# ServoControllerCircuit.net
KiCad netlist of a schematic drawn in EAGLE
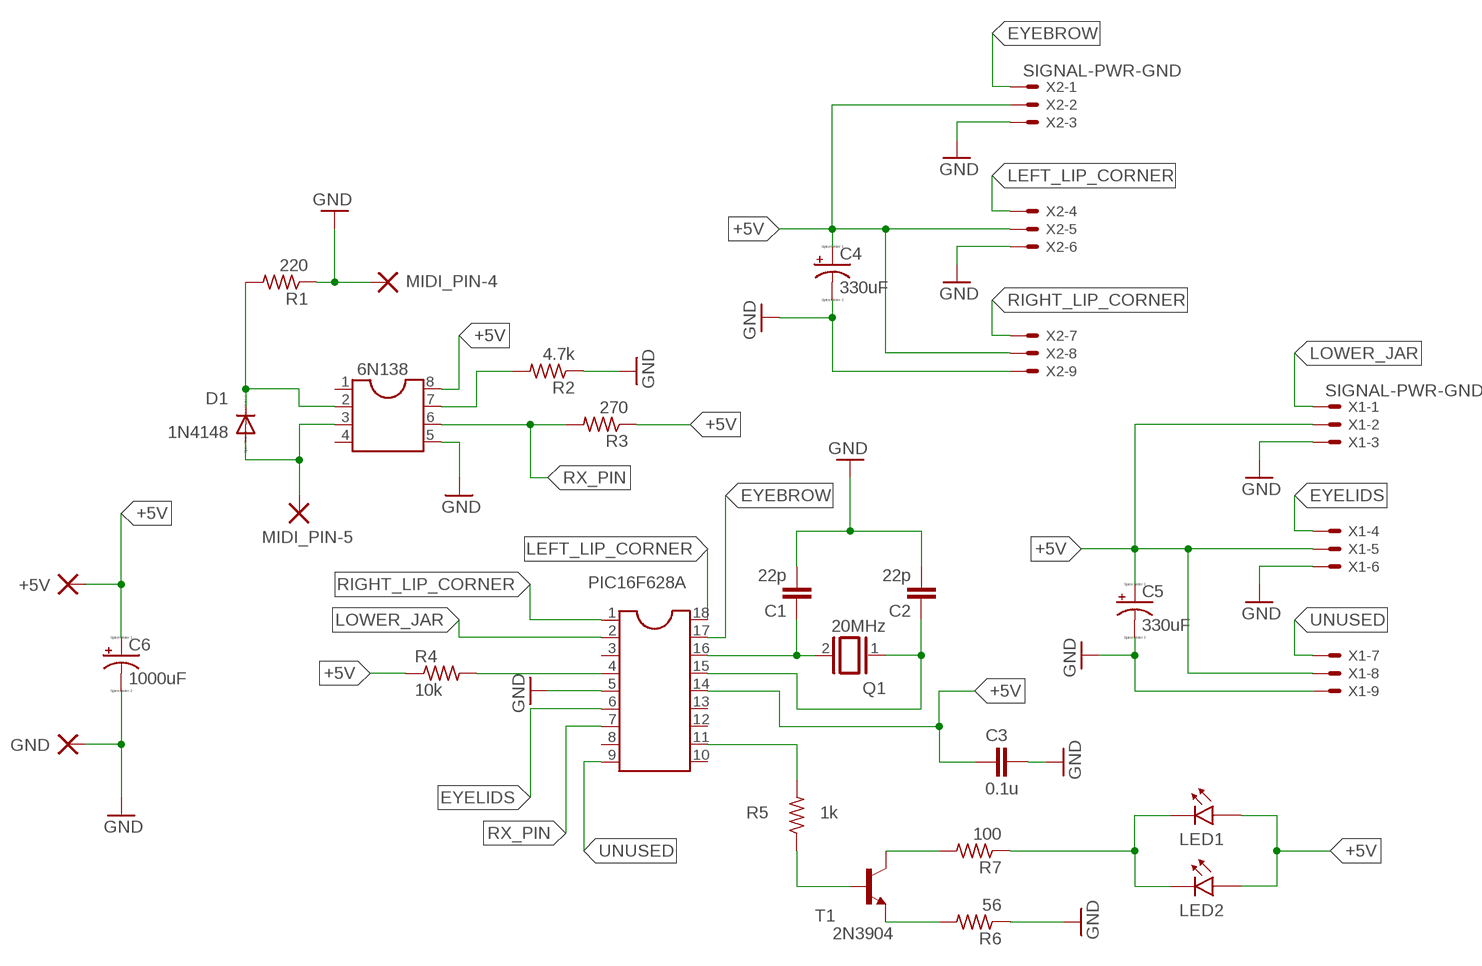
[diagram p0: schematic, sheet 1]

(export (version "E")
  (design (tool "Eeschema 10.0.6"))
  (components
    (comp (ref "+5V")
      (value "DOUBLE_THROUGH_HOLE_PAD")
      (footprint "eagle-import:DOUBLE_THROUGH_HOLE_PAD")
      (libsource (lib "eagle-import") (part "DOUBLE_THROUGH_HOLE_PAD"))
    )
    (comp (ref "6N138")
      (value "DIL8S")
      (footprint "eagle-import:SOCKET-08")
      (libsource (lib "eagle-import") (part "DIL8S"))
    )
    (comp (ref "C1")
      (value "22p")
      (footprint "eagle-import:C050-025X075")
      (libsource (lib "eagle-import") (part "C-EU050-025X075"))
    )
    (comp (ref "C2")
      (value "22p")
      (footprint "eagle-import:C050-025X075")
      (libsource (lib "eagle-import") (part "C-EU050-025X075"))
    )
    (comp (ref "C3")
      (value "0.1u")
      (footprint "eagle-import:C050-025X075")
      (libsource (lib "eagle-import") (part "C-EU050-025X075"))
    )
    (comp (ref "C4")
      (value "330uF")
      (footprint "eagle-import:E3,5-8")
      (libsource (lib "eagle-import") (part "CPOL-USE3.5-8"))
    )
    (comp (ref "C5")
      (value "330uF")
      (footprint "eagle-import:E3,5-8")
      (libsource (lib "eagle-import") (part "CPOL-USE3.5-8"))
    )
    (comp (ref "C6")
      (value "1000uF")
      (footprint "eagle-import:E5-10,5")
      (libsource (lib "eagle-import") (part "CPOL-USE5-10.5"))
    )
    (comp (ref "D1")
      (value "1N4148")
      (footprint "eagle-import:DO35-10")
      (libsource (lib "eagle-import") (part "1N4148DO35-10"))
    )
    (comp (ref "GND")
      (value "DOUBLE_THROUGH_HOLE_PAD")
      (footprint "eagle-import:DOUBLE_THROUGH_HOLE_PAD")
      (libsource (lib "eagle-import") (part "DOUBLE_THROUGH_HOLE_PAD"))
    )
    (comp (ref "LED1")
      (value "REMOTE_LED")
      (footprint "eagle-import:REMOTE_LED")
      (libsource (lib "eagle-import") (part "REMOTE_LED"))
    )
    (comp (ref "LED2")
      (value "REMOTE_LED")
      (footprint "eagle-import:REMOTE_LED")
      (libsource (lib "eagle-import") (part "REMOTE_LED"))
    )
    (comp (ref "MIDI_PIN-4")
      (value "DOUBLE_THROUGH_HOLE_PAD")
      (footprint "eagle-import:DOUBLE_THROUGH_HOLE_PAD")
      (libsource (lib "eagle-import") (part "DOUBLE_THROUGH_HOLE_PAD"))
    )
    (comp (ref "MIDI_PIN-5")
      (value "DOUBLE_THROUGH_HOLE_PAD")
      (footprint "eagle-import:DOUBLE_THROUGH_HOLE_PAD")
      (libsource (lib "eagle-import") (part "DOUBLE_THROUGH_HOLE_PAD"))
    )
    (comp (ref "PIC16F628A")
      (value "DIL18S")
      (footprint "eagle-import:SOCKET-18")
      (libsource (lib "eagle-import") (part "DIL18S"))
    )
    (comp (ref "Q1")
      (value "20MHz")
      (footprint "eagle-import:QS")
      (libsource (lib "eagle-import") (part "XTAL/S"))
    )
    (comp (ref "R1")
      (value "220")
      (footprint "eagle-import:0207_12")
      (libsource (lib "eagle-import") (part "R-US_0207/12"))
    )
    (comp (ref "R2")
      (value "4.7k")
      (footprint "eagle-import:0207_12")
      (libsource (lib "eagle-import") (part "R-US_0207/12"))
    )
    (comp (ref "R3")
      (value "270")
      (footprint "eagle-import:0207_12")
      (libsource (lib "eagle-import") (part "R-US_0207/12"))
    )
    (comp (ref "R4")
      (value "10k")
      (footprint "eagle-import:0207_12")
      (libsource (lib "eagle-import") (part "R-US_0207/12"))
    )
    (comp (ref "R5")
      (value "1k")
      (footprint "eagle-import:0207_12")
      (libsource (lib "eagle-import") (part "R-US_0207/12"))
    )
    (comp (ref "R6")
      (value "56")
      (footprint "eagle-import:0207_12")
      (libsource (lib "eagle-import") (part "R-US_0207/12"))
    )
    (comp (ref "R7")
      (value "100")
      (footprint "eagle-import:0207_12")
      (libsource (lib "eagle-import") (part "R-US_0207/12"))
    )
    (comp (ref "T1")
      (value "2N3904")
      (footprint "eagle-import:TO92")
      (libsource (lib "eagle-import") (part "2N3904"))
    )
    (comp (ref "X1")
      (value "SIGNAL-PWR-GND")
      (footprint "eagle-import:22-23-2091")
      (fields (field (name "MF") "MOLEX") (field (name "MPN") "22-23-2091"))
      (libsource (lib "eagle-import") (part "22-23-2091"))
    )
    (comp (ref "X2")
      (value "SIGNAL-PWR-GND")
      (footprint "eagle-import:22-23-2091")
      (fields (field (name "MF") "MOLEX") (field (name "MPN") "22-23-2091"))
      (libsource (lib "eagle-import") (part "22-23-2091"))
    )
  )
  (nets
    (net (code "1") (name "+5V") (class "Default")
      (node (ref "+5V") (pin "P$1") (pinfunction "P$1_P$1") (pintype "bidirectional"))
      (node (ref "6N138") (pin "8") (pinfunction "8_8") (pintype "passive"))
      (node (ref "C3") (pin "2") (pinfunction "2_2") (pintype "passive"))
      (node (ref "C4") (pin "+") (pinfunction "+_+") (pintype "passive"))
      (node (ref "C5") (pin "+") (pinfunction "+_+") (pintype "passive"))
      (node (ref "C6") (pin "+") (pinfunction "+_+") (pintype "passive"))
      (node (ref "LED1") (pin "P$1") (pinfunction "P$1_P$1") (pintype "bidirectional"))
      (node (ref "LED2") (pin "P$1") (pinfunction "P$1_P$1") (pintype "bidirectional"))
      (node (ref "PIC16F628A") (pin "14") (pinfunction "14_14") (pintype "passive"))
      (node (ref "R3") (pin "1") (pinfunction "1_1") (pintype "passive"))
      (node (ref "R4") (pin "1") (pinfunction "1_1") (pintype "passive"))
      (node (ref "X1") (pin "2") (pinfunction "S_2") (pintype "passive"))
      (node (ref "X1") (pin "5") (pinfunction "S_5") (pintype "passive"))
      (node (ref "X1") (pin "8") (pinfunction "S_8") (pintype "passive"))
      (node (ref "X2") (pin "2") (pinfunction "S_2") (pintype "passive"))
      (node (ref "X2") (pin "5") (pinfunction "S_5") (pintype "passive"))
      (node (ref "X2") (pin "8") (pinfunction "S_8") (pintype "passive"))
    )
    (net (code "2") (name "EYEBROW") (class "Default")
      (node (ref "PIC16F628A") (pin "17") (pinfunction "17_17") (pintype "passive"))
      (node (ref "X2") (pin "1") (pinfunction "S_1") (pintype "passive"))
    )
    (net (code "3") (name "EYELIDS") (class "Default")
      (node (ref "PIC16F628A") (pin "6") (pinfunction "6_6") (pintype "passive"))
      (node (ref "X1") (pin "4") (pinfunction "S_4") (pintype "passive"))
    )
    (net (code "4") (name "GND") (class "Default")
      (node (ref "6N138") (pin "5") (pinfunction "5_5") (pintype "passive"))
      (node (ref "C1") (pin "2") (pinfunction "2_2") (pintype "passive"))
      (node (ref "C2") (pin "2") (pinfunction "2_2") (pintype "passive"))
      (node (ref "C3") (pin "1") (pinfunction "1_1") (pintype "passive"))
      (node (ref "C4") (pin "-") (pinfunction "-_-") (pintype "passive"))
      (node (ref "C5") (pin "-") (pinfunction "-_-") (pintype "passive"))
      (node (ref "C6") (pin "-") (pinfunction "-_-") (pintype "passive"))
      (node (ref "GND") (pin "P$1") (pinfunction "P$1_P$1") (pintype "bidirectional"))
      (node (ref "MIDI_PIN-4") (pin "P$1") (pinfunction "P$1_P$1") (pintype "bidirectional"))
      (node (ref "PIC16F628A") (pin "5") (pinfunction "5_5") (pintype "passive"))
      (node (ref "R1") (pin "1") (pinfunction "1_1") (pintype "passive"))
      (node (ref "R2") (pin "1") (pinfunction "1_1") (pintype "passive"))
      (node (ref "R6") (pin "1") (pinfunction "1_1") (pintype "passive"))
      (node (ref "X1") (pin "3") (pinfunction "S_3") (pintype "passive"))
      (node (ref "X1") (pin "6") (pinfunction "S_6") (pintype "passive"))
      (node (ref "X1") (pin "9") (pinfunction "S_9") (pintype "passive"))
      (node (ref "X2") (pin "3") (pinfunction "S_3") (pintype "passive"))
      (node (ref "X2") (pin "6") (pinfunction "S_6") (pintype "passive"))
      (node (ref "X2") (pin "9") (pinfunction "S_9") (pintype "passive"))
    )
    (net (code "5") (name "LEFT_LIP_CORNER") (class "Default")
      (node (ref "PIC16F628A") (pin "18") (pinfunction "18_18") (pintype "passive"))
      (node (ref "X2") (pin "4") (pinfunction "S_4") (pintype "passive"))
    )
    (net (code "6") (name "LOWER_JAR") (class "Default")
      (node (ref "PIC16F628A") (pin "2") (pinfunction "2_2") (pintype "passive"))
      (node (ref "X1") (pin "1") (pinfunction "S_1") (pintype "passive"))
    )
    (net (code "7") (name "Net-(6N138-Pad2)") (class "Default")
      (node (ref "6N138") (pin "2") (pinfunction "2_2") (pintype "passive"))
      (node (ref "D1") (pin "C") (pinfunction "C_C") (pintype "passive"))
      (node (ref "R1") (pin "2") (pinfunction "2_2") (pintype "passive"))
    )
    (net (code "8") (name "Net-(6N138-Pad3)") (class "Default")
      (node (ref "6N138") (pin "3") (pinfunction "3_3") (pintype "passive"))
      (node (ref "D1") (pin "A") (pinfunction "A_A") (pintype "passive"))
      (node (ref "MIDI_PIN-5") (pin "P$1") (pinfunction "P$1_P$1") (pintype "bidirectional"))
    )
    (net (code "9") (name "Net-(6N138-Pad7)") (class "Default")
      (node (ref "6N138") (pin "7") (pinfunction "7_7") (pintype "passive"))
      (node (ref "R2") (pin "2") (pinfunction "2_2") (pintype "passive"))
    )
    (net (code "10") (name "Net-(C1-Pad1)") (class "Default")
      (node (ref "C1") (pin "1") (pinfunction "1_1") (pintype "passive"))
      (node (ref "PIC16F628A") (pin "16") (pinfunction "16_16") (pintype "passive"))
      (node (ref "Q1") (pin "2") (pinfunction "2_2") (pintype "passive"))
    )
    (net (code "11") (name "Net-(C2-Pad1)") (class "Default")
      (node (ref "C2") (pin "1") (pinfunction "1_1") (pintype "passive"))
      (node (ref "PIC16F628A") (pin "15") (pinfunction "15_15") (pintype "passive"))
      (node (ref "Q1") (pin "1") (pinfunction "1_1") (pintype "passive"))
    )
    (net (code "12") (name "Net-(LED1-PadP$2)") (class "Default")
      (node (ref "LED1") (pin "P$2") (pinfunction "P$2_P$2") (pintype "bidirectional"))
      (node (ref "LED2") (pin "P$2") (pinfunction "P$2_P$2") (pintype "bidirectional"))
      (node (ref "R7") (pin "1") (pinfunction "1_1") (pintype "passive"))
    )
    (net (code "13") (name "Net-(PIC16F628A-Pad4)") (class "Default")
      (node (ref "PIC16F628A") (pin "4") (pinfunction "4_4") (pintype "passive"))
      (node (ref "R4") (pin "2") (pinfunction "2_2") (pintype "passive"))
    )
    (net (code "14") (name "Net-(PIC16F628A-Pad11)") (class "Default")
      (node (ref "PIC16F628A") (pin "11") (pinfunction "11_11") (pintype "passive"))
      (node (ref "R5") (pin "2") (pinfunction "2_2") (pintype "passive"))
    )
    (net (code "15") (name "Net-(T1-B)") (class "Default")
      (node (ref "R5") (pin "1") (pinfunction "1_1") (pintype "passive"))
      (node (ref "T1") (pin "2") (pinfunction "B_2") (pintype "passive"))
    )
    (net (code "16") (name "Net-(T1-C)") (class "Default")
      (node (ref "R7") (pin "2") (pinfunction "2_2") (pintype "passive"))
      (node (ref "T1") (pin "1") (pinfunction "C_1") (pintype "passive"))
    )
    (net (code "17") (name "Net-(T1-E)") (class "Default")
      (node (ref "R6") (pin "2") (pinfunction "2_2") (pintype "passive"))
      (node (ref "T1") (pin "3") (pinfunction "E_3") (pintype "passive"))
    )
    (net (code "18") (name "RIGHT_LIP_CORNER") (class "Default")
      (node (ref "PIC16F628A") (pin "1") (pinfunction "1_1") (pintype "passive"))
      (node (ref "X2") (pin "7") (pinfunction "S_7") (pintype "passive"))
    )
    (net (code "19") (name "RX_PIN") (class "Default")
      (node (ref "6N138") (pin "6") (pinfunction "6_6") (pintype "passive"))
      (node (ref "PIC16F628A") (pin "7") (pinfunction "7_7") (pintype "passive"))
      (node (ref "R3") (pin "2") (pinfunction "2_2") (pintype "passive"))
    )
    (net (code "20") (name "UNUSED") (class "Default")
      (node (ref "PIC16F628A") (pin "9") (pinfunction "9_9") (pintype "passive"))
      (node (ref "X1") (pin "7") (pinfunction "S_7") (pintype "passive"))
    )
    (net (code "21") (name "unconnected-(6N138-Pad1)") (class "Default")
      (node (ref "6N138") (pin "1") (pinfunction "1_1") (pintype "passive"))
    )
    (net (code "22") (name "unconnected-(6N138-Pad4)") (class "Default")
      (node (ref "6N138") (pin "4") (pinfunction "4_4") (pintype "passive"))
    )
    (net (code "23") (name "unconnected-(PIC16F628A-Pad3)") (class "Default")
      (node (ref "PIC16F628A") (pin "3") (pinfunction "3_3") (pintype "passive"))
    )
    (net (code "24") (name "unconnected-(PIC16F628A-Pad8)") (class "Default")
      (node (ref "PIC16F628A") (pin "8") (pinfunction "8_8") (pintype "passive"))
    )
    (net (code "25") (name "unconnected-(PIC16F628A-Pad10)") (class "Default")
      (node (ref "PIC16F628A") (pin "10") (pinfunction "10_10") (pintype "passive"))
    )
    (net (code "26") (name "unconnected-(PIC16F628A-Pad12)") (class "Default")
      (node (ref "PIC16F628A") (pin "12") (pinfunction "12_12") (pintype "passive"))
    )
    (net (code "27") (name "unconnected-(PIC16F628A-Pad13)") (class "Default")
      (node (ref "PIC16F628A") (pin "13") (pinfunction "13_13") (pintype "passive"))
    )
  )
)
